# LPC55S69_MINI_A.net
KiCad netlist of a schematic drawn in Altium Designer
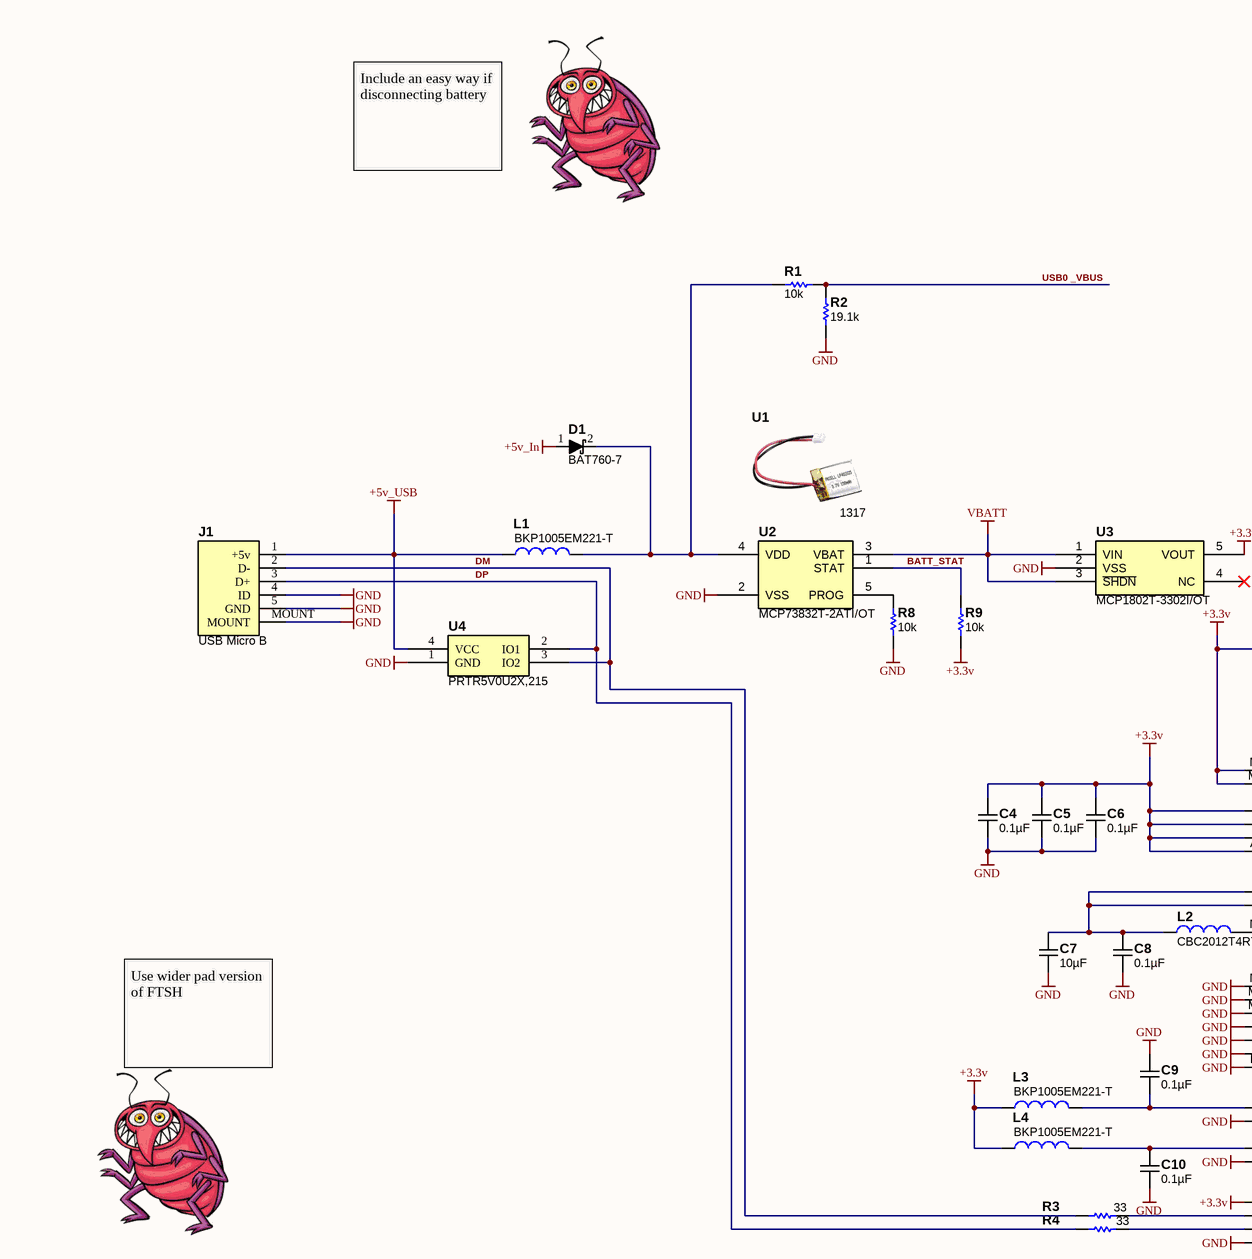
[diagram p0: LPC55S69_MINI [A].SchDoc, top left]
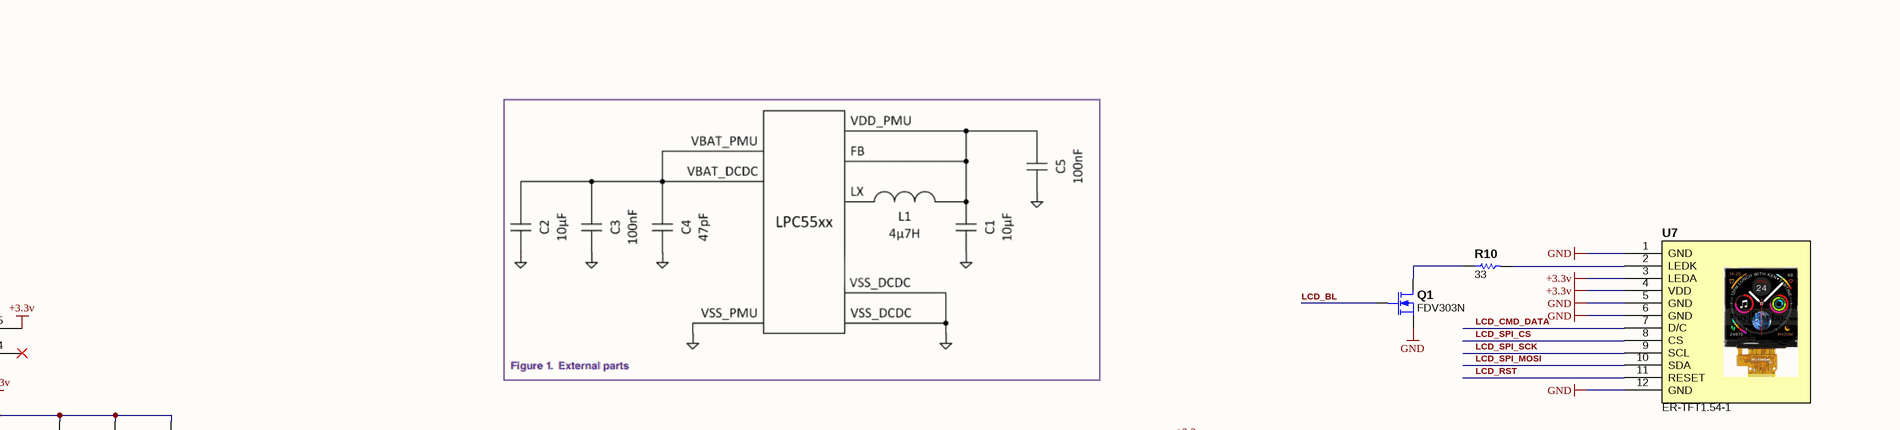
[diagram p1: LPC55S69_MINI [A].SchDoc, top right]
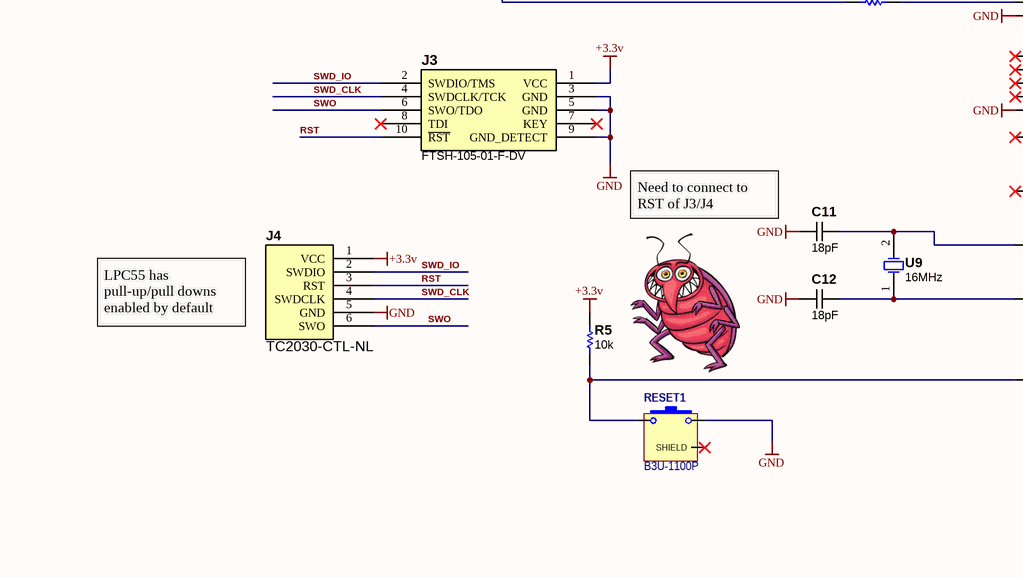
[diagram p2: LPC55S69_MINI [A].SchDoc, bottom left]
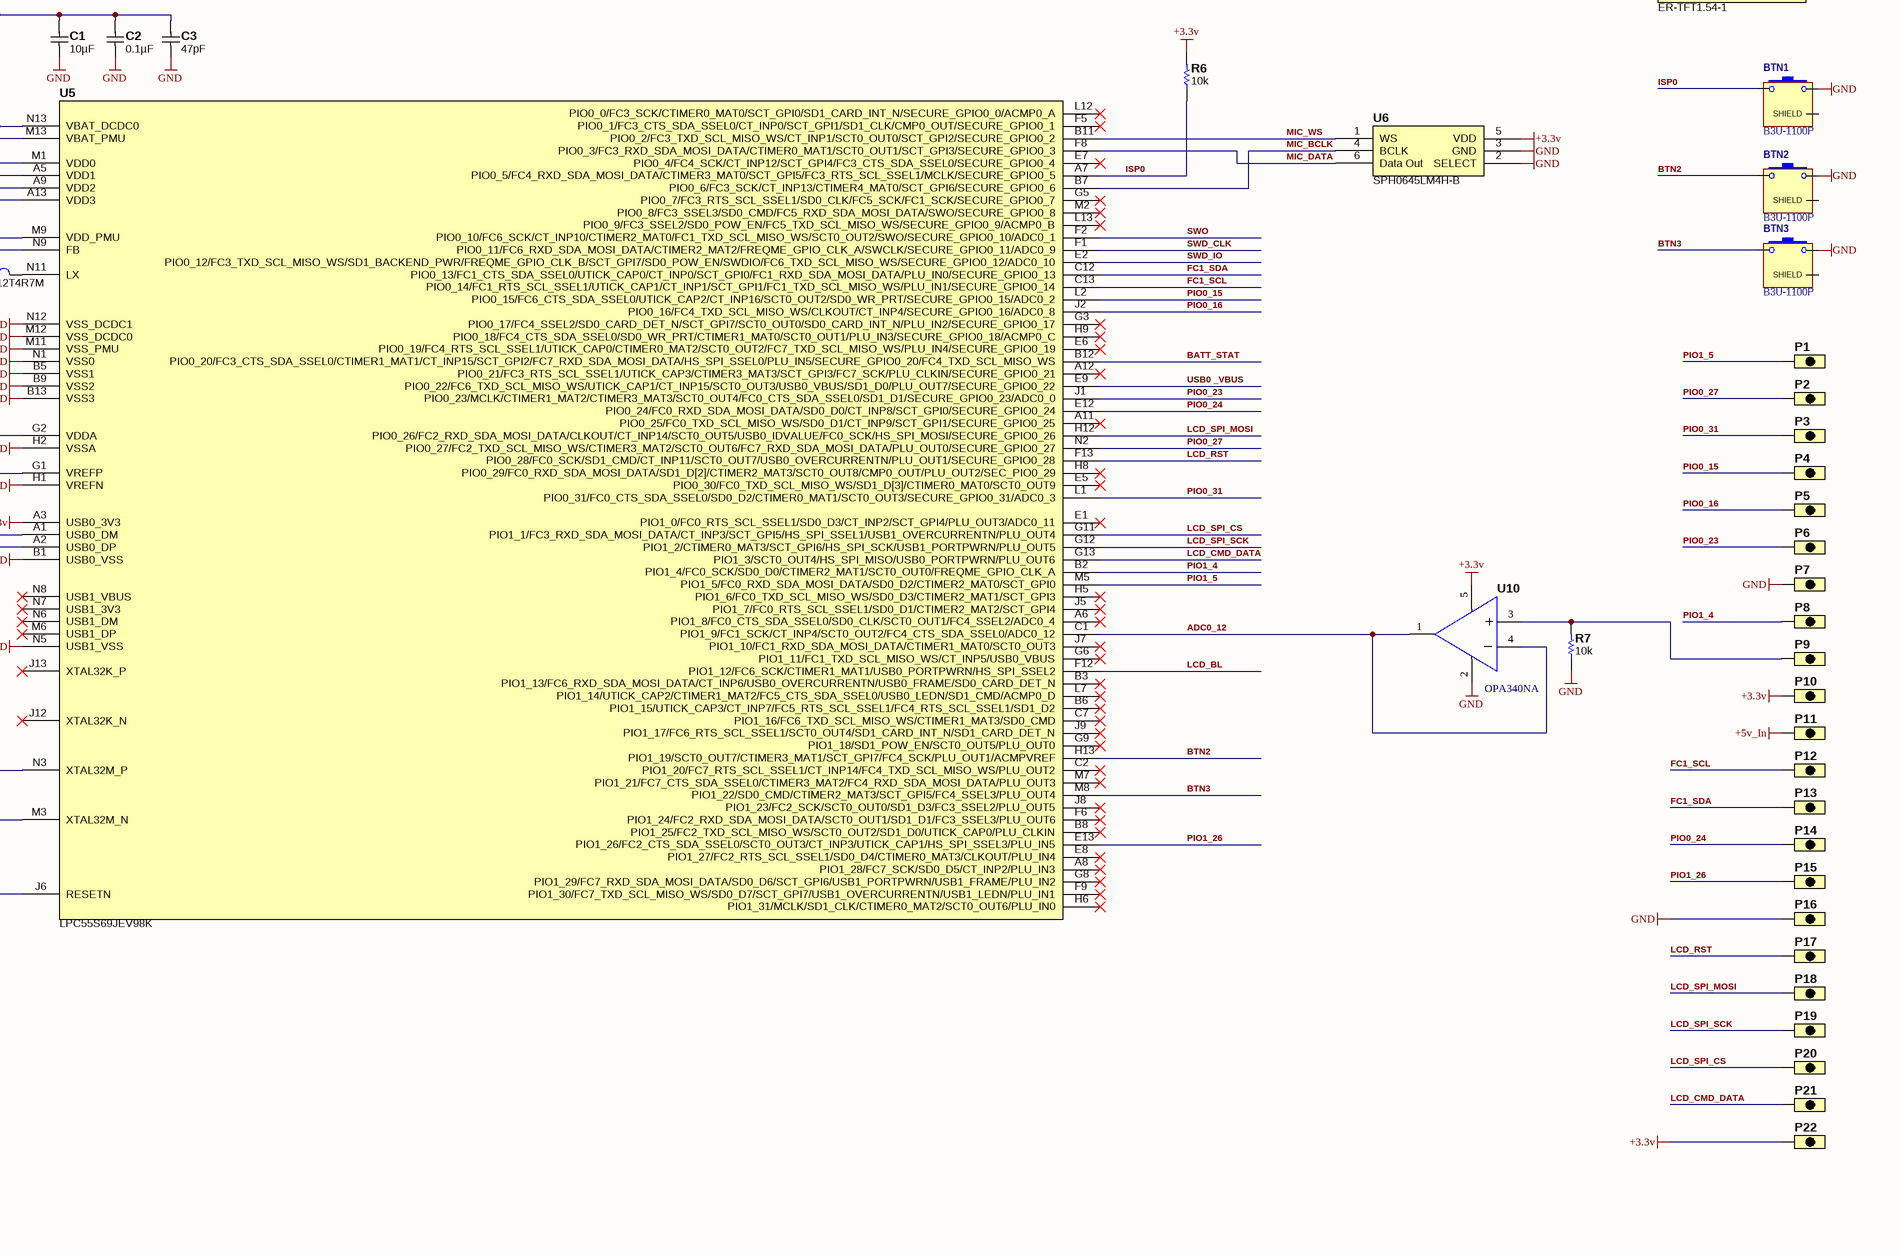
[diagram p3: LPC55S69_MINI [A].SchDoc, bottom right]

(export (version "E")
  (design (tool "Eeschema 10.0.6"))
  (components
    (comp (ref "BTN1")
      (value "B3U-1100P")
      (footprint "OMRON_B3U-1100P")
      (description "SWITCH TACTILE SPST-NO 0.05A 12V")
      (fields (field (name "MANUFACTURER") "Omron Electronics Inc-EMC Div"))
      (libsource (lib "Switches-N") (part "B3U-1100P"))
    )
    (comp (ref "BTN2")
      (value "B3U-1100P")
      (footprint "OMRON_B3U-1100P")
      (description "SWITCH TACTILE SPST-NO 0.05A 12V")
      (fields (field (name "MANUFACTURER") "Omron Electronics Inc-EMC Div"))
      (libsource (lib "Switches-N") (part "B3U-1100P"))
    )
    (comp (ref "BTN3")
      (value "B3U-1100P")
      (footprint "OMRON_B3U-1100P")
      (description "SWITCH TACTILE SPST-NO 0.05A 12V")
      (fields (field (name "MANUFACTURER") "Omron Electronics Inc-EMC Div"))
      (libsource (lib "Switches-N") (part "B3U-1100P"))
    )
    (comp (ref "C1")
      (value "10µF")
      (footprint "C0805_1.45MM_MD")
      (description "CAP CER 10UF 6.3V X7R 0805")
      (fields
        (field (name "MANUFACTURER PART NUMBER") "CGA4J1X7R0J106K125AC")
        (field (name "MANUFACTURER") "TDK Corporation")
      )
      (libsource (lib "Capacitors - TDK- AEC-Q200") (part "C_2P_NP"))
    )
    (comp (ref "C2")
      (value "0.1µF")
      (footprint "C0402_0.55MM_MD")
      (description "CAP CER 0.1UF 16V X7R 0402")
      (fields
        (field (name "MANUFACTURER PART NUMBER") "CGA2B1X7R1C104K050BC")
        (field (name "MANUFACTURER") "TDK Corporation")
      )
      (libsource (lib "Capacitors - TDK- AEC-Q200") (part "C_2P_NP"))
    )
    (comp (ref "C3")
      (value "47pF")
      (footprint "C0402_0.55MM_MD")
      (description "CAP CER 47PF 50V C0G 0402")
      (fields
        (field (name "MANUFACTURER PART NUMBER") "CGA2B2C0G1H470J050BA")
        (field (name "MANUFACTURER") "TDK Corporation")
      )
      (libsource (lib "Capacitors - TDK- AEC-Q200") (part "C_2P_NP"))
    )
    (comp (ref "C4")
      (value "0.1µF")
      (footprint "C0402_0.55MM_MD")
      (description "CAP CER 0.1UF 16V X7R 0402")
      (fields
        (field (name "MANUFACTURER PART NUMBER") "CGA2B1X7R1C104K050BC")
        (field (name "MANUFACTURER") "TDK Corporation")
      )
      (libsource (lib "Capacitors - TDK- AEC-Q200") (part "C_2P_NP"))
    )
    (comp (ref "C5")
      (value "0.1µF")
      (footprint "C0402_0.55MM_MD")
      (description "CAP CER 0.1UF 16V X7R 0402")
      (fields
        (field (name "MANUFACTURER PART NUMBER") "CGA2B1X7R1C104K050BC")
        (field (name "MANUFACTURER") "TDK Corporation")
      )
      (libsource (lib "Capacitors - TDK- AEC-Q200") (part "C_2P_NP"))
    )
    (comp (ref "C6")
      (value "0.1µF")
      (footprint "C0402_0.55MM_MD")
      (description "CAP CER 0.1UF 16V X7R 0402")
      (fields
        (field (name "MANUFACTURER PART NUMBER") "CGA2B1X7R1C104K050BC")
        (field (name "MANUFACTURER") "TDK Corporation")
      )
      (libsource (lib "Capacitors - TDK- AEC-Q200") (part "C_2P_NP"))
    )
    (comp (ref "C7")
      (value "10µF")
      (footprint "C0805_1.45MM_MD")
      (description "CAP CER 10UF 6.3V X7R 0805")
      (fields
        (field (name "MANUFACTURER PART NUMBER") "CGA4J1X7R0J106K125AC")
        (field (name "MANUFACTURER") "TDK Corporation")
      )
      (libsource (lib "Capacitors - TDK- AEC-Q200") (part "C_2P_NP"))
    )
    (comp (ref "C8")
      (value "0.1µF")
      (footprint "C0402_0.55MM_MD")
      (description "CAP CER 0.1UF 16V X7R 0402")
      (fields
        (field (name "MANUFACTURER PART NUMBER") "CGA2B1X7R1C104K050BC")
        (field (name "MANUFACTURER") "TDK Corporation")
      )
      (libsource (lib "Capacitors - TDK- AEC-Q200") (part "C_2P_NP"))
    )
    (comp (ref "C9")
      (value "0.1µF")
      (footprint "C0402_0.55MM_MD")
      (description "CAP CER 0.1UF 16V X7R 0402")
      (fields
        (field (name "MANUFACTURER PART NUMBER") "CGA2B1X7R1C104K050BC")
        (field (name "MANUFACTURER") "TDK Corporation")
      )
      (libsource (lib "Capacitors - TDK- AEC-Q200") (part "C_2P_NP"))
    )
    (comp (ref "C10")
      (value "0.1µF")
      (footprint "C0402_0.55MM_MD")
      (description "CAP CER 0.1UF 16V X7R 0402")
      (fields
        (field (name "MANUFACTURER PART NUMBER") "CGA2B1X7R1C104K050BC")
        (field (name "MANUFACTURER") "TDK Corporation")
      )
      (libsource (lib "Capacitors - TDK- AEC-Q200") (part "C_2P_NP"))
    )
    (comp (ref "C11")
      (value "18pF")
      (footprint "C0402_0.55MM_MD")
      (description "CAP CER 18PF 50V C0G 0402")
      (fields
        (field (name "MANUFACTURER PART NUMBER") "CGA2B2C0G1H180J050BA")
        (field (name "MANUFACTURER") "TDK Corporation")
      )
      (libsource (lib "Capacitors - TDK- AEC-Q200") (part "C_2P_NP"))
    )
    (comp (ref "C12")
      (value "18pF")
      (footprint "C0402_0.55MM_MD")
      (description "CAP CER 18PF 50V C0G 0402")
      (fields
        (field (name "MANUFACTURER PART NUMBER") "CGA2B2C0G1H180J050BA")
        (field (name "MANUFACTURER") "TDK Corporation")
      )
      (libsource (lib "Capacitors - TDK- AEC-Q200") (part "C_2P_NP"))
    )
    (comp (ref "D1")
      (value "BAT760-7")
      (footprint "D_SOD-323_P")
      (description "DIODE SCHOTTKY 30V 1A SOD323")
      (fields (field (name "MANUFACTURER") "Diodes Inc"))
      (libsource (lib "Diodes") (part "DS_1A_2C"))
    )
    (comp (ref "J1")
      (value "USB Micro B")
      (footprint "10103594-0001LF")
      (description "CONN RCPT STD MICRO USB TYPE B")
      (fields (field (name "MANUFACTURER") "FCI") (field (name "MANUFACTURER PART NUMBER") "10103594-0001LF"))
      (libsource (lib "eConnector_USB") (part "10103594-0001LF"))
    )
    (comp (ref "J3")
      (value "FTSH-105-01-F-DV")
      (footprint "FTSH-105-04-F-DV - HD - NO_STEP")
      (description "SAMTEC - FTSH-105-01-F-DV - .050 X .050")
      (fields (field (name "MANUFACTURER") "SAMTEC"))
      (libsource (lib "eConnector") (part "CORTEX-DEBUG"))
    )
    (comp (ref "J4")
      (value "TC2030‐CTL‐NL")
      (footprint "TC2030 NO LATCH")
      (description "Tag Connect Pads - No latching Clips - ARM")
      (libsource (lib "eConnector") (part "TC2030‐CTL‐NL"))
    )
    (comp (ref "L1")
      (value "BKP1005EM221-T")
      (footprint "C0402_HD")
      (description "FERRITE BEAD 220 OHM 0402 1LN")
      (fields (field (name "MANUFACTURER") "Taiyo Yuden"))
      (libsource (lib "eInductor") (part "BKP1005EM221-T"))
    )
    (comp (ref "L2")
      (value "CBC2012T4R7M")
      (footprint "C0805_1.45MM_MD")
      (description "FIXED IND 4.7UH 520MA 650 MOHM")
      (fields (field (name "MANUFACTURER") "Taiyo Yuden") (field (name "TOLERANCE") "20%"))
      (libsource (lib "eInductor") (part "CBC2012T4R7M"))
    )
    (comp (ref "L3")
      (value "BKP1005EM221-T")
      (footprint "C0402_HD")
      (description "FERRITE BEAD 220 OHM 0402 1LN")
      (fields (field (name "MANUFACTURER") "Taiyo Yuden"))
      (libsource (lib "eInductor") (part "BKP1005EM221-T"))
    )
    (comp (ref "L4")
      (value "BKP1005EM221-T")
      (footprint "C0402_HD")
      (description "FERRITE BEAD 220 OHM 0402 1LN")
      (fields (field (name "MANUFACTURER") "Taiyo Yuden"))
      (libsource (lib "eInductor") (part "BKP1005EM221-T"))
    )
    (comp (ref "P1")
      (value "~")
      (footprint "CASTELLATED")
      (libsource (lib "eConnector") (part "CASTELLATED"))
    )
    (comp (ref "P2")
      (value "~")
      (footprint "CASTELLATED")
      (libsource (lib "eConnector") (part "CASTELLATED"))
    )
    (comp (ref "P3")
      (value "~")
      (footprint "CASTELLATED")
      (libsource (lib "eConnector") (part "CASTELLATED"))
    )
    (comp (ref "P4")
      (value "~")
      (footprint "CASTELLATED")
      (libsource (lib "eConnector") (part "CASTELLATED"))
    )
    (comp (ref "P5")
      (value "~")
      (footprint "CASTELLATED")
      (libsource (lib "eConnector") (part "CASTELLATED"))
    )
    (comp (ref "P6")
      (value "~")
      (footprint "CASTELLATED")
      (libsource (lib "eConnector") (part "CASTELLATED"))
    )
    (comp (ref "P7")
      (value "~")
      (footprint "CASTELLATED")
      (libsource (lib "eConnector") (part "CASTELLATED"))
    )
    (comp (ref "P8")
      (value "~")
      (footprint "CASTELLATED")
      (libsource (lib "eConnector") (part "CASTELLATED"))
    )
    (comp (ref "P9")
      (value "~")
      (footprint "CASTELLATED")
      (libsource (lib "eConnector") (part "CASTELLATED"))
    )
    (comp (ref "P10")
      (value "~")
      (footprint "CASTELLATED")
      (libsource (lib "eConnector") (part "CASTELLATED"))
    )
    (comp (ref "P11")
      (value "~")
      (footprint "CASTELLATED")
      (libsource (lib "eConnector") (part "CASTELLATED"))
    )
    (comp (ref "P12")
      (value "~")
      (footprint "CASTELLATED")
      (libsource (lib "eConnector") (part "CASTELLATED"))
    )
    (comp (ref "P13")
      (value "~")
      (footprint "CASTELLATED")
      (libsource (lib "eConnector") (part "CASTELLATED"))
    )
    (comp (ref "P14")
      (value "~")
      (footprint "CASTELLATED")
      (libsource (lib "eConnector") (part "CASTELLATED"))
    )
    (comp (ref "P15")
      (value "~")
      (footprint "CASTELLATED")
      (libsource (lib "eConnector") (part "CASTELLATED"))
    )
    (comp (ref "P16")
      (value "~")
      (footprint "CASTELLATED")
      (libsource (lib "eConnector") (part "CASTELLATED"))
    )
    (comp (ref "P17")
      (value "~")
      (footprint "CASTELLATED")
      (libsource (lib "eConnector") (part "CASTELLATED"))
    )
    (comp (ref "P18")
      (value "~")
      (footprint "CASTELLATED")
      (libsource (lib "eConnector") (part "CASTELLATED"))
    )
    (comp (ref "P19")
      (value "~")
      (footprint "CASTELLATED")
      (libsource (lib "eConnector") (part "CASTELLATED"))
    )
    (comp (ref "P20")
      (value "~")
      (footprint "CASTELLATED")
      (libsource (lib "eConnector") (part "CASTELLATED"))
    )
    (comp (ref "P21")
      (value "~")
      (footprint "CASTELLATED")
      (libsource (lib "eConnector") (part "CASTELLATED"))
    )
    (comp (ref "P22")
      (value "~")
      (footprint "CASTELLATED")
      (libsource (lib "eConnector") (part "CASTELLATED"))
    )
    (comp (ref "Q1")
      (value "FDV303N")
      (footprint "SOT-23")
      (description "MOSFET N-CH 25V 680MA SOT-23")
      (fields (field (name "MANUFACTURER") "Fairchild Semiconductor") (field (name "SOURCE") "Digikey"))
      (libsource (lib "eTransistor") (part "FDV303N"))
    )
    (comp (ref "R1")
      (value "10k")
      (footprint "R0402_0.40MM_MD")
      (description "RES 10K OHM 1/10W 1% 0402 SMD")
      (fields
        (field (name "MANUFACTURER PART NUMBER") "ERJ-2RKF1002X")
        (field (name "MANUFACTURER") "Panasonic Electronic Components")
      )
      (libsource (lib "Resistors - Panasonic - AEC-Q200") (part "R_2P"))
    )
    (comp (ref "R2")
      (value "19.1k")
      (footprint "R0402_0.40MM_MD")
      (description "RES 19.1K OHM 1/10W 1% 0402 SMD")
      (fields
        (field (name "MANUFACTURER PART NUMBER") "ERJ-2RKF1912X")
        (field (name "MANUFACTURER") "Panasonic Electronic Components")
      )
      (libsource (lib "Resistors - Panasonic - AEC-Q200") (part "R_2P"))
    )
    (comp (ref "R3")
      (value "33")
      (footprint "R0603_0.55MM_MD")
      (description "RES 33 OHM 1/10W 1% 0603 SMD")
      (fields
        (field (name "MANUFACTURER PART NUMBER") "ERJ-3EKF33R0V")
        (field (name "MANUFACTURER") "Panasonic Electronic Components")
      )
      (libsource (lib "Resistors - Panasonic - AEC-Q200") (part "R_2P"))
    )
    (comp (ref "R4")
      (value "33")
      (footprint "R0603_0.55MM_MD")
      (description "RES 33 OHM 1/10W 1% 0603 SMD")
      (fields
        (field (name "MANUFACTURER PART NUMBER") "ERJ-3EKF33R0V")
        (field (name "MANUFACTURER") "Panasonic Electronic Components")
      )
      (libsource (lib "Resistors - Panasonic - AEC-Q200") (part "R_2P"))
    )
    (comp (ref "R5")
      (value "10k")
      (footprint "R0402_0.40MM_MD")
      (description "RES 10K OHM 1/10W 1% 0402 SMD")
      (fields
        (field (name "MANUFACTURER PART NUMBER") "ERJ-2RKF1002X")
        (field (name "MANUFACTURER") "Panasonic Electronic Components")
      )
      (libsource (lib "Resistors - Panasonic - AEC-Q200") (part "R_2P"))
    )
    (comp (ref "R6")
      (value "10k")
      (footprint "R0402_0.40MM_MD")
      (description "RES 10K OHM 1/10W 1% 0402 SMD")
      (fields
        (field (name "MANUFACTURER PART NUMBER") "ERJ-2RKF1002X")
        (field (name "MANUFACTURER") "Panasonic Electronic Components")
      )
      (libsource (lib "Resistors - Panasonic - AEC-Q200") (part "R_2P"))
    )
    (comp (ref "R7")
      (value "10k")
      (footprint "R0402_0.40MM_MD")
      (description "RES 10K OHM 1/10W 1% 0402 SMD")
      (fields
        (field (name "MANUFACTURER PART NUMBER") "ERJ-2RKF1002X")
        (field (name "MANUFACTURER") "Panasonic Electronic Components")
      )
      (libsource (lib "Resistors - Panasonic - AEC-Q200") (part "R_2P"))
    )
    (comp (ref "R8")
      (value "10k")
      (footprint "R0402_0.40MM_MD")
      (description "RES 10K OHM 1/10W 1% 0402 SMD")
      (fields
        (field (name "MANUFACTURER PART NUMBER") "ERJ-2RKF1002X")
        (field (name "MANUFACTURER") "Panasonic Electronic Components")
      )
      (libsource (lib "Resistors - Panasonic - AEC-Q200") (part "R_2P"))
    )
    (comp (ref "R9")
      (value "10k")
      (footprint "R0402_0.40MM_MD")
      (description "RES 10K OHM 1/10W 1% 0402 SMD")
      (fields
        (field (name "MANUFACTURER PART NUMBER") "ERJ-2RKF1002X")
        (field (name "MANUFACTURER") "Panasonic Electronic Components")
      )
      (libsource (lib "Resistors - Panasonic - AEC-Q200") (part "R_2P"))
    )
    (comp (ref "R10")
      (value "33")
      (footprint "R0603_0.55MM_MD")
      (description "RES 33 OHM 1/10W 1% 0603 SMD")
      (fields
        (field (name "MANUFACTURER PART NUMBER") "ERJ-3EKF33R0V")
        (field (name "MANUFACTURER") "Panasonic Electronic Components")
      )
      (libsource (lib "Resistors - Panasonic - AEC-Q200") (part "R_2P"))
    )
    (comp (ref "RESET1")
      (value "B3U-1100P")
      (footprint "OMRON_B3U-1100P")
      (description "SWITCH TACTILE SPST-NO 0.05A 12V")
      (fields (field (name "MANUFACTURER") "Omron Electronics Inc-EMC Div"))
      (libsource (lib "Switches-N") (part "B3U-1100P"))
    )
    (comp (ref "U1")
      (value "1317")
      (footprint "LIPO-150MAH")
      (description "FLORA LI-PO BATTERY 3.7V 150MAH")
      (fields (field (name "MANUFACTURER") "Adafruit Industries"))
      (libsource (lib "eBattery") (part "1317"))
    )
    (comp (ref "U2")
      (value "MCP73832T-2ATI/OT")
      (footprint "SOT23-5")
      (description "Charge Controller Li-Ion/Li-Pol 15mA to 500mA 4.2V 5-Pin SOT-23 T/R")
      (fields (field (name "MANUFACTURER") "Microchip"))
      (libsource (lib "eIC") (part "MCP73832T-2ATI/OT"))
    )
    (comp (ref "U3")
      (value "MCP1802T-3302I/OT")
      (footprint "SOT23-5")
      (description "IC REG LINEAR 3.3V 300MA SOT23-5")
      (fields (field (name "MANUFACTURER") "Microchip"))
      (libsource (lib "eIC_Regulator") (part "MCP1802T-3302I/OT"))
    )
    (comp (ref "U4")
      (value "PRTR5V0U2X,215")
      (footprint "SOT143B")
      (description "TVS DIODE 5.5VWM SOT143B")
      (fields (field (name "MANUFACTURER") "NXP Semiconductors"))
      (libsource (lib "eDiode") (part "PRTR5V0U2X,215"))
    )
    (comp (ref "U5")
      (value "LPC55S69JEV98K")
      (footprint "98-VFBGA")
      (description "IC MCU 100MHZ CORTEX M33 DUAL")
      (fields (field (name "MANUFACTURER") "NXP Semiconductors"))
      (libsource (lib "eIC") (part "LPC55S69JEV98K"))
    )
    (comp (ref "U6")
      (value "SPH0645LM4H-B")
      (footprint "SPH0645LM4H-B")
      (fields (field (name "MANUFACTURER") "Knowles Acoustics"))
      (libsource (lib "eAudio") (part "SPH0645LM4H-B"))
    )
    (comp (ref "U7")
      (value "ER-TFT1.54-1")
      (footprint "ER-TFT1.54-1")
      (description "1.54\" 240x240 IPS Display")
      (fields (field (name "MANUFACTURER") "Buy Display"))
      (libsource (lib "eDisplay") (part "ER-TFT1.54-1"))
    )
    (comp (ref "U9")
      (value "16MHz")
      (footprint "ABM3")
      (description "Crystal 16MHz ±20ppm (Tol) ±50ppm (Stability) 18pF FUND 50Ohm 2-Pin CSMD T/R")
      (fields
        (field (name "MANUFACTURER") "Abracon")
        (field (name "MANUFACTURER PART NUMBER") "ABM3-16.000MHZ-B2-T")
      )
      (libsource (lib "eCrystal") (part "ABM3-16.000MHZ-B2-T"))
    )
    (comp (ref "U10")
      (value "OPA340NA")
      (footprint "SOT95P245X145-5L")
      (description "IC SINGLE SUPPLY OPAMP SOT-23-5")
      (fields
        (field (name "MANUFACTURER") "Texas Instruments")
        (field (name "MANUFACTURER PART NUMBER") "OPA340NA/250")
        (field (name "SOURCE") "Digikey")
      )
      (libsource (lib "eOPAMP") (part "OPA340"))
    )
  )
  (nets
    (net (code "1") (name "+3.3v") (class "Default")
      (node (ref "C1") (pin "2") (pinfunction "1_2") (pintype "passive"))
      (node (ref "C2") (pin "2") (pinfunction "1_2") (pintype "passive"))
      (node (ref "C3") (pin "2") (pinfunction "1_2") (pintype "passive"))
      (node (ref "C4") (pin "2") (pinfunction "1_2") (pintype "passive"))
      (node (ref "C5") (pin "2") (pinfunction "1_2") (pintype "passive"))
      (node (ref "C6") (pin "2") (pinfunction "1_2") (pintype "passive"))
      (node (ref "J3") (pin "1") (pinfunction "VCC_1") (pintype "passive"))
      (node (ref "J4") (pin "1") (pinfunction "VCC_1") (pintype "passive"))
      (node (ref "L3") (pin "1") (pinfunction "1_1") (pintype "passive"))
      (node (ref "L4") (pin "1") (pinfunction "1_1") (pintype "passive"))
      (node (ref "P10") (pin "1") (pinfunction "1_1") (pintype "passive"))
      (node (ref "P22") (pin "1") (pinfunction "1_1") (pintype "passive"))
      (node (ref "R5") (pin "2") (pinfunction "2_2") (pintype "passive"))
      (node (ref "R6") (pin "2") (pinfunction "2_2") (pintype "passive"))
      (node (ref "R9") (pin "1") (pinfunction "1_1") (pintype "passive"))
      (node (ref "U10") (pin "5") (pinfunction "VCC_5") (pintype "passive"))
      (node (ref "U3") (pin "5") (pinfunction "VOUT_5") (pintype "passive"))
      (node (ref "U5") (pin "A13") (pinfunction "VDD3_A13") (pintype "passive"))
      (node (ref "U5") (pin "A3") (pinfunction "USB0_3V3_A3") (pintype "passive"))
      (node (ref "U5") (pin "A5") (pinfunction "VDD1_A5") (pintype "passive"))
      (node (ref "U5") (pin "A9") (pinfunction "VDD2_A9") (pintype "passive"))
      (node (ref "U5") (pin "M1") (pinfunction "VDD0_M1") (pintype "passive"))
      (node (ref "U5") (pin "M13") (pinfunction "VBAT_PMU_M13") (pintype "passive"))
      (node (ref "U5") (pin "N13") (pinfunction "VBAT_DCDC0_N13") (pintype "passive"))
      (node (ref "U6") (pin "5") (pinfunction "VDD_5") (pintype "passive"))
      (node (ref "U7") (pin "3") (pinfunction "LEDA_3") (pintype "passive"))
      (node (ref "U7") (pin "4") (pinfunction "VDD_4") (pintype "passive"))
    )
    (net (code "2") (name "+5v_In") (class "Default")
      (node (ref "D1") (pin "1") (pinfunction "A_1") (pintype "passive"))
      (node (ref "P11") (pin "1") (pinfunction "1_1") (pintype "passive"))
    )
    (net (code "3") (name "+5v_USB") (class "Default")
      (node (ref "J1") (pin "1") (pinfunction "+5v_1") (pintype "passive"))
      (node (ref "L1") (pin "1") (pinfunction "1_1") (pintype "passive"))
      (node (ref "U4") (pin "4") (pinfunction "VCC_4") (pintype "passive"))
    )
    (net (code "4") (name "/ADC0_12") (class "Default")
      (node (ref "U10") (pin "1") (pinfunction "OUT_1") (pintype "passive"))
      (node (ref "U10") (pin "4") (pinfunction "-_4") (pintype "passive"))
      (node (ref "U5") (pin "C1") (pinfunction "PIO1_9/FC1_SCK/CT_INP4/SCT0_OUT2/FC4_CTS_SDA_SSEL0/ADC0_12_C1") (pintype "passive"))
    )
    (net (code "5") (name "/BATT_STAT") (class "Default")
      (node (ref "R9") (pin "2") (pinfunction "2_2") (pintype "passive"))
      (node (ref "U2") (pin "1") (pinfunction "STAT_1") (pintype "passive"))
      (node (ref "U5") (pin "B12") (pinfunction "PIO0_20/FC3_CTS_SDA_SSEL0/CTIMER1_MAT1/CT_INP15/SCT_GPI2/FC7_RXD_SDA_MOSI_DATA/HS_SPI_SSEL0/PLU_IN5/SECURE_GPIO0_20/FC4_TXD_SCL_MISO_WS_B12") (pintype "passive"))
    )
    (net (code "6") (name "/BTN2") (class "Default")
      (node (ref "BTN2") (pin "2") (pinfunction "2_2") (pintype "passive"))
      (node (ref "U5") (pin "H13") (pinfunction "PIO1_19/SCT0_OUT7/CTIMER3_MAT1/SCT_GPI7/FC4_SCK/PLU_OUT1/ACMPVREF_H13") (pintype "passive"))
    )
    (net (code "7") (name "/BTN3") (class "Default")
      (node (ref "BTN3") (pin "2") (pinfunction "2_2") (pintype "passive"))
      (node (ref "U5") (pin "M8") (pinfunction "PIO1_22/SD0_CMD/CTIMER2_MAT3/SCT_GPI5/FC4_SSEL3/PLU_OUT4_M8") (pintype "passive"))
    )
    (net (code "8") (name "/DM") (class "Default")
      (node (ref "J1") (pin "2") (pinfunction "D-_2") (pintype "passive"))
      (node (ref "R3") (pin "1") (pinfunction "1_1") (pintype "passive"))
      (node (ref "U4") (pin "3") (pinfunction "IO2_3") (pintype "passive"))
    )
    (net (code "9") (name "/DP") (class "Default")
      (node (ref "J1") (pin "3") (pinfunction "D+_3") (pintype "passive"))
      (node (ref "R4") (pin "1") (pinfunction "1_1") (pintype "passive"))
      (node (ref "U4") (pin "2") (pinfunction "IO1_2") (pintype "passive"))
    )
    (net (code "10") (name "/FC1_SCL") (class "Default")
      (node (ref "P12") (pin "1") (pinfunction "1_1") (pintype "passive"))
      (node (ref "U5") (pin "C13") (pinfunction "PIO0_14/FC1_RTS_SCL_SSEL1/UTICK_CAP1/CT_INP1/SCT_GPI1/FC1_TXD_SCL_MISO_WS/PLU_IN1/SECURE_GPIO0_14_C13") (pintype "passive"))
    )
    (net (code "11") (name "/FC1_SDA") (class "Default")
      (node (ref "P13") (pin "1") (pinfunction "1_1") (pintype "passive"))
      (node (ref "U5") (pin "C12") (pinfunction "PIO0_13/FC1_CTS_SDA_SSEL0/UTICK_CAP0/CT_INP0/SCT_GPI0/FC1_RXD_SDA_MOSI_DATA/PLU_IN0/SECURE_GPIO0_13_C12") (pintype "passive"))
    )
    (net (code "12") (name "/ISP0") (class "Default")
      (node (ref "BTN1") (pin "2") (pinfunction "2_2") (pintype "passive"))
      (node (ref "R6") (pin "1") (pinfunction "1_1") (pintype "passive"))
      (node (ref "U5") (pin "A7") (pinfunction "PIO0_5/FC4_RXD_SDA_MOSI_DATA/CTIMER3_MAT0/SCT_GPI5/FC3_RTS_SCL_SSEL1/MCLK/SECURE_GPIO0_5_A7") (pintype "passive"))
    )
    (net (code "13") (name "/LCD_BL") (class "Default")
      (node (ref "Q1") (pin "1") (pinfunction "G_1") (pintype "passive"))
      (node (ref "U5") (pin "F12") (pinfunction "PIO1_12/FC6_SCK/CTIMER1_MAT1/USB0_PORTPWRN/HS_SPI_SSEL2_F12") (pintype "passive"))
    )
    (net (code "14") (name "/LCD_CMD_DATA") (class "Default")
      (node (ref "P21") (pin "1") (pinfunction "1_1") (pintype "passive"))
      (node (ref "U5") (pin "G13") (pinfunction "PIO1_3/SCT0_OUT4/HS_SPI_MISO/USB0_PORTPWRN/PLU_OUT6_G13") (pintype "passive"))
      (node (ref "U7") (pin "7") (pinfunction "D/C_7") (pintype "passive"))
    )
    (net (code "15") (name "/LCD_RST") (class "Default")
      (node (ref "P17") (pin "1") (pinfunction "1_1") (pintype "passive"))
      (node (ref "U5") (pin "F13") (pinfunction "PIO0_28/FC0_SCK/SD1_CMD/CT_INP11/SCT0_OUT7/USB0_OVERCURRENTN/PLU_OUT1/SECURE_GPIO0_28_F13") (pintype "passive"))
      (node (ref "U7") (pin "11") (pinfunction "RESET_11") (pintype "passive"))
    )
    (net (code "16") (name "/LCD_SPI_CS") (class "Default")
      (node (ref "P20") (pin "1") (pinfunction "1_1") (pintype "passive"))
      (node (ref "U5") (pin "G11") (pinfunction "PIO1_1/FC3_RXD_SDA_MOSI_DATA/CT_INP3/SCT_GPI5/HS_SPI_SSEL1/USB1_OVERCURRENTN/PLU_OUT4_G11") (pintype "passive"))
      (node (ref "U7") (pin "8") (pinfunction "CS_8") (pintype "passive"))
    )
    (net (code "17") (name "/LCD_SPI_MOSI") (class "Default")
      (node (ref "P18") (pin "1") (pinfunction "1_1") (pintype "passive"))
      (node (ref "U5") (pin "H12") (pinfunction "PIO0_26/FC2_RXD_SDA_MOSI_DATA/CLKOUT/CT_INP14/SCT0_OUT5/USB0_IDVALUE/FC0_SCK/HS_SPI_MOSI/SECURE_GPIO0_26_H12") (pintype "passive"))
      (node (ref "U7") (pin "10") (pinfunction "SDA_10") (pintype "passive"))
    )
    (net (code "18") (name "/LCD_SPI_SCK") (class "Default")
      (node (ref "P19") (pin "1") (pinfunction "1_1") (pintype "passive"))
      (node (ref "U5") (pin "G12") (pinfunction "PIO1_2/CTIMER0_MAT3/SCT_GPI6/HS_SPI_SCK/USB1_PORTPWRN/PLU_OUT5_G12") (pintype "passive"))
      (node (ref "U7") (pin "9") (pinfunction "SCL_9") (pintype "passive"))
    )
    (net (code "19") (name "/MIC_BCLK") (class "Default")
      (node (ref "U5") (pin "B7") (pinfunction "PIO0_6/FC3_SCK/CT_INP13/CTIMER4_MAT0/SCT_GPI6/SECURE_GPIO0_6_B7") (pintype "passive"))
      (node (ref "U6") (pin "4") (pinfunction "BCLK_4") (pintype "passive"))
    )
    (net (code "20") (name "/MIC_DATA") (class "Default")
      (node (ref "U5") (pin "F8") (pinfunction "PIO0_3/FC3_RXD_SDA_MOSI_DATA/CTIMER0_MAT1/SCT0_OUT1/SCT_GPI3/SECURE_GPIO0_3_F8") (pintype "passive"))
      (node (ref "U6") (pin "6") (pinfunction "Data_Out_6") (pintype "passive"))
    )
    (net (code "21") (name "/MIC_WS") (class "Default")
      (node (ref "U5") (pin "B11") (pinfunction "PIO0_2/FC3_TXD_SCL_MISO_WS/CT_INP1/SCT0_OUT0/SCT_GPI2/SECURE_GPIO0_2_B11") (pintype "passive"))
      (node (ref "U6") (pin "1") (pinfunction "WS_1") (pintype "passive"))
    )
    (net (code "22") (name "/PIO0_15") (class "Default")
      (node (ref "P4") (pin "1") (pinfunction "1_1") (pintype "passive"))
      (node (ref "U5") (pin "L2") (pinfunction "PIO0_15/FC6_CTS_SDA_SSEL0/UTICK_CAP2/CT_INP16/SCT0_OUT2/SD0_WR_PRT/SECURE_GPIO0_15/ADC0_2_L2") (pintype "passive"))
    )
    (net (code "23") (name "/PIO0_16") (class "Default")
      (node (ref "P5") (pin "1") (pinfunction "1_1") (pintype "passive"))
      (node (ref "U5") (pin "J2") (pinfunction "PIO0_16/FC4_TXD_SCL_MISO_WS/CLKOUT/CT_INP4/SECURE_GPIO0_16/ADC0_8_J2") (pintype "passive"))
    )
    (net (code "24") (name "/PIO0_23") (class "Default")
      (node (ref "P6") (pin "1") (pinfunction "1_1") (pintype "passive"))
      (node (ref "U5") (pin "J1") (pinfunction "PIO0_23/MCLK/CTIMER1_MAT2/CTIMER3_MAT3/SCT0_OUT4/FC0_CTS_SDA_SSEL0/SD1_D1/SECURE_GPIO0_23/ADC0_0_J1") (pintype "passive"))
    )
    (net (code "25") (name "/PIO0_24") (class "Default")
      (node (ref "P14") (pin "1") (pinfunction "1_1") (pintype "passive"))
      (node (ref "U5") (pin "E12") (pinfunction "PIO0_24/FC0_RXD_SDA_MOSI_DATA/SD0_D0/CT_INP8/SCT_GPI0/SECURE_GPIO0_24_E12") (pintype "passive"))
    )
    (net (code "26") (name "/PIO0_27") (class "Default")
      (node (ref "P2") (pin "1") (pinfunction "1_1") (pintype "passive"))
      (node (ref "U5") (pin "N2") (pinfunction "PIO0_27/FC2_TXD_SCL_MISO_WS/CTIMER3_MAT2/SCT0_OUT6/FC7_RXD_SDA_MOSI_DATA/PLU_OUT0/SECURE_GPIO0_27_N2") (pintype "passive"))
    )
    (net (code "27") (name "/PIO0_31") (class "Default")
      (node (ref "P3") (pin "1") (pinfunction "1_1") (pintype "passive"))
      (node (ref "U5") (pin "L1") (pinfunction "PIO0_31/FC0_CTS_SDA_SSEL0/SD0_D2/CTIMER0_MAT1/SCT0_OUT3/SECURE_GPIO0_31/ADC0_3_L1") (pintype "passive"))
    )
    (net (code "28") (name "/PIO1_4") (class "Default")
      (node (ref "P8") (pin "1") (pinfunction "1_1") (pintype "passive"))
      (node (ref "U5") (pin "B2") (pinfunction "PIO1_4/FC0_SCK/SD0_D0/CTIMER2_MAT1/SCT0_OUT0/FREQME_GPIO_CLK_A_B2") (pintype "passive"))
    )
    (net (code "29") (name "/PIO1_5") (class "Default")
      (node (ref "P1") (pin "1") (pinfunction "1_1") (pintype "passive"))
      (node (ref "U5") (pin "M5") (pinfunction "PIO1_5/FC0_RXD_SDA_MOSI_DATA/SD0_D2/CTIMER2_MAT0/SCT_GPI0_M5") (pintype "passive"))
    )
    (net (code "30") (name "/PIO1_26") (class "Default")
      (node (ref "P15") (pin "1") (pinfunction "1_1") (pintype "passive"))
      (node (ref "U5") (pin "E13") (pinfunction "PIO1_26/FC2_CTS_SDA_SSEL0/SCT0_OUT3/CT_INP3/UTICK_CAP1/HS_SPI_SSEL3/PLU_IN5_E13") (pintype "passive"))
    )
    (net (code "31") (name "/RST") (class "Default")
      (node (ref "J3") (pin "10") (pinfunction "~{RST}_10") (pintype "passive"))
      (node (ref "J4") (pin "3") (pinfunction "RST_3") (pintype "passive"))
    )
    (net (code "32") (name "/SWD_CLK") (class "Default")
      (node (ref "J3") (pin "4") (pinfunction "SWDCLK/TCK_4") (pintype "passive"))
      (node (ref "J4") (pin "4") (pinfunction "SWDCLK_4") (pintype "passive"))
      (node (ref "U5") (pin "F1") (pinfunction "PIO0_11/FC6_RXD_SDA_MOSI_DATA/CTIMER2_MAT2/FREQME_GPIO_CLK_A/SWCLK/SECURE_GPIO0_11/ADC0_9_F1") (pintype "passive"))
    )
    (net (code "33") (name "/SWD_IO") (class "Default")
      (node (ref "J3") (pin "2") (pinfunction "SWDIO/TMS_2") (pintype "passive"))
      (node (ref "J4") (pin "2") (pinfunction "SWDIO_2") (pintype "passive"))
      (node (ref "U5") (pin "E2") (pinfunction "PIO0_12/FC3_TXD_SCL_MISO_WS/SD1_BACKEND_PWR/FREQME_GPIO_CLK_B/SCT_GPI7/SD0_POW_EN/SWDIO/FC6_TXD_SCL_MISO_WS/SECURE_GPIO0_12/ADC0_10_E2") (pintype "passive"))
    )
    (net (code "34") (name "/SWO") (class "Default")
      (node (ref "J3") (pin "6") (pinfunction "SWO/TDO_6") (pintype "passive"))
      (node (ref "J4") (pin "6") (pinfunction "SWO_6") (pintype "passive"))
      (node (ref "U5") (pin "F2") (pinfunction "PIO0_10/FC6_SCK/CT_INP10/CTIMER2_MAT0/FC1_TXD_SCL_MISO_WS/SCT0_OUT2/SWO/SECURE_GPIO0_10/ADC0_1_F2") (pintype "passive"))
    )
    (net (code "35") (name "/USB0 _VBUS") (class "Default")
      (node (ref "R1") (pin "2") (pinfunction "2_2") (pintype "passive"))
      (node (ref "R2") (pin "2") (pinfunction "2_2") (pintype "passive"))
      (node (ref "U5") (pin "E9") (pinfunction "PIO0_22/FC6_TXD_SCL_MISO_WS/UTICK_CAP1/CT_INP15/SCT0_OUT3/USB0_VBUS/SD1_D0/PLU_OUT7/SECURE_GPIO0_22_E9") (pintype "passive"))
    )
    (net (code "36") (name "GND") (class "Default")
      (node (ref "BTN1") (pin "1") (pinfunction "1_1") (pintype "passive"))
      (node (ref "BTN2") (pin "1") (pinfunction "1_1") (pintype "passive"))
      (node (ref "BTN3") (pin "1") (pinfunction "1_1") (pintype "passive"))
      (node (ref "C1") (pin "1") (pinfunction "1_1") (pintype "passive"))
      (node (ref "C10") (pin "1") (pinfunction "1_1") (pintype "passive"))
      (node (ref "C11") (pin "1") (pinfunction "1_1") (pintype "passive"))
      (node (ref "C12") (pin "1") (pinfunction "1_1") (pintype "passive"))
      (node (ref "C2") (pin "1") (pinfunction "1_1") (pintype "passive"))
      (node (ref "C3") (pin "1") (pinfunction "1_1") (pintype "passive"))
      (node (ref "C4") (pin "1") (pinfunction "1_1") (pintype "passive"))
      (node (ref "C5") (pin "1") (pinfunction "1_1") (pintype "passive"))
      (node (ref "C6") (pin "1") (pinfunction "1_1") (pintype "passive"))
      (node (ref "C7") (pin "1") (pinfunction "1_1") (pintype "passive"))
      (node (ref "C8") (pin "1") (pinfunction "1_1") (pintype "passive"))
      (node (ref "C9") (pin "2") (pinfunction "1_2") (pintype "passive"))
      (node (ref "J1") (pin "4") (pinfunction "ID_4") (pintype "passive"))
      (node (ref "J1") (pin "5") (pinfunction "GND_5") (pintype "passive"))
      (node (ref "J1") (pin "MOUNT") (pinfunction "MOUNT_MOUNT") (pintype "passive"))
      (node (ref "J3") (pin "3") (pinfunction "GND_3") (pintype "passive"))
      (node (ref "J3") (pin "5") (pinfunction "GND_5") (pintype "passive"))
      (node (ref "J3") (pin "9") (pinfunction "GND_DETECT_9") (pintype "passive"))
      (node (ref "J4") (pin "5") (pinfunction "GND_5") (pintype "passive"))
      (node (ref "P16") (pin "1") (pinfunction "1_1") (pintype "passive"))
      (node (ref "P7") (pin "1") (pinfunction "1_1") (pintype "passive"))
      (node (ref "Q1") (pin "2") (pinfunction "S_2") (pintype "passive"))
      (node (ref "R2") (pin "1") (pinfunction "1_1") (pintype "passive"))
      (node (ref "R7") (pin "1") (pinfunction "1_1") (pintype "passive"))
      (node (ref "R8") (pin "1") (pinfunction "1_1") (pintype "passive"))
      (node (ref "RESET1") (pin "1") (pinfunction "1_1") (pintype "passive"))
      (node (ref "U10") (pin "2") (pinfunction "GND_2") (pintype "passive"))
      (node (ref "U2") (pin "2") (pinfunction "VSS_2") (pintype "passive"))
      (node (ref "U3") (pin "2") (pinfunction "VSS_2") (pintype "passive"))
      (node (ref "U4") (pin "1") (pinfunction "GND_1") (pintype "passive"))
      (node (ref "U5") (pin "B1") (pinfunction "USB0_VSS_B1") (pintype "passive"))
      (node (ref "U5") (pin "B13") (pinfunction "VSS3_B13") (pintype "passive"))
      (node (ref "U5") (pin "B5") (pinfunction "VSS1_B5") (pintype "passive"))
      (node (ref "U5") (pin "B9") (pinfunction "VSS2_B9") (pintype "passive"))
      (node (ref "U5") (pin "H1") (pinfunction "VREFN_H1") (pintype "passive"))
      (node (ref "U5") (pin "H2") (pinfunction "VSSA_H2") (pintype "passive"))
      (node (ref "U5") (pin "M11") (pinfunction "VSS_PMU_M11") (pintype "passive"))
      (node (ref "U5") (pin "M12") (pinfunction "VSS_DCDC0_M12") (pintype "passive"))
      (node (ref "U5") (pin "N1") (pinfunction "VSS0_N1") (pintype "passive"))
      (node (ref "U5") (pin "N12") (pinfunction "VSS_DCDC1_N12") (pintype "passive"))
      (node (ref "U5") (pin "N5") (pinfunction "USB1_VSS_N5") (pintype "passive"))
      (node (ref "U6") (pin "2") (pinfunction "SELECT_2") (pintype "passive"))
      (node (ref "U6") (pin "3") (pinfunction "GND_3") (pintype "passive"))
      (node (ref "U7") (pin "1") (pinfunction "GND_1") (pintype "passive"))
      (node (ref "U7") (pin "12") (pinfunction "GND_12") (pintype "passive"))
      (node (ref "U7") (pin "5") (pinfunction "GND_5") (pintype "passive"))
      (node (ref "U7") (pin "6") (pinfunction "GND_6") (pintype "passive"))
    )
    (net (code "37") (name "Net-(D1-K)") (class "Default")
      (node (ref "D1") (pin "2") (pinfunction "K_2") (pintype "passive"))
      (node (ref "L1") (pin "2") (pinfunction "2_2") (pintype "passive"))
      (node (ref "R1") (pin "1") (pinfunction "1_1") (pintype "passive"))
      (node (ref "U2") (pin "4") (pinfunction "VDD_4") (pintype "passive"))
    )
    (net (code "38") (name "Net-(Q1-D)") (class "Default")
      (node (ref "Q1") (pin "3") (pinfunction "D_3") (pintype "passive"))
      (node (ref "R10") (pin "1") (pinfunction "1_1") (pintype "passive"))
    )
    (net (code "39") (name "Net-(U2-PROG)") (class "Default")
      (node (ref "R8") (pin "2") (pinfunction "2_2") (pintype "passive"))
      (node (ref "U2") (pin "5") (pinfunction "PROG_5") (pintype "passive"))
    )
    (net (code "40") (name "Net-(U5-FB)") (class "Default")
      (node (ref "C7") (pin "2") (pinfunction "1_2") (pintype "passive"))
      (node (ref "C8") (pin "2") (pinfunction "1_2") (pintype "passive"))
      (node (ref "L2") (pin "1") (pinfunction "1_1") (pintype "passive"))
      (node (ref "U5") (pin "M9") (pinfunction "VDD_PMU_M9") (pintype "passive"))
      (node (ref "U5") (pin "N9") (pinfunction "FB_N9") (pintype "passive"))
    )
    (net (code "41") (name "Net-(U5-LX)") (class "Default")
      (node (ref "L2") (pin "2") (pinfunction "2_2") (pintype "passive"))
      (node (ref "U5") (pin "N11") (pinfunction "LX_N11") (pintype "passive"))
    )
    (net (code "42") (name "Net-(U5-RESETN)") (class "Default")
      (node (ref "R5") (pin "1") (pinfunction "1_1") (pintype "passive"))
      (node (ref "RESET1") (pin "2") (pinfunction "2_2") (pintype "passive"))
      (node (ref "U5") (pin "J6") (pinfunction "RESETN_J6") (pintype "passive"))
    )
    (net (code "43") (name "Net-(U5-USB0_DM)") (class "Default")
      (node (ref "R3") (pin "2") (pinfunction "2_2") (pintype "passive"))
      (node (ref "U5") (pin "A1") (pinfunction "USB0_DM_A1") (pintype "passive"))
    )
    (net (code "44") (name "Net-(U5-USB0_DP)") (class "Default")
      (node (ref "R4") (pin "2") (pinfunction "2_2") (pintype "passive"))
      (node (ref "U5") (pin "A2") (pinfunction "USB0_DP_A2") (pintype "passive"))
    )
    (net (code "45") (name "Net-(U5-VDDA)") (class "Default")
      (node (ref "C9") (pin "1") (pinfunction "1_1") (pintype "passive"))
      (node (ref "L3") (pin "2") (pinfunction "2_2") (pintype "passive"))
      (node (ref "U5") (pin "G2") (pinfunction "VDDA_G2") (pintype "passive"))
    )
    (net (code "46") (name "Net-(U5-VREFP)") (class "Default")
      (node (ref "C10") (pin "2") (pinfunction "1_2") (pintype "passive"))
      (node (ref "L4") (pin "2") (pinfunction "2_2") (pintype "passive"))
      (node (ref "U5") (pin "G1") (pinfunction "VREFP_G1") (pintype "passive"))
    )
    (net (code "47") (name "Net-(U5-XTAL32M_N)") (class "Default")
      (node (ref "C12") (pin "2") (pinfunction "1_2") (pintype "passive"))
      (node (ref "U5") (pin "M3") (pinfunction "XTAL32M_N_M3") (pintype "passive"))
      (node (ref "U9") (pin "1") (pinfunction "OSC1_1") (pintype "passive"))
    )
    (net (code "48") (name "Net-(U5-XTAL32M_P)") (class "Default")
      (node (ref "C11") (pin "2") (pinfunction "1_2") (pintype "passive"))
      (node (ref "U5") (pin "N3") (pinfunction "XTAL32M_P_N3") (pintype "passive"))
      (node (ref "U9") (pin "2") (pinfunction "OSC2_2") (pintype "passive"))
    )
    (net (code "49") (name "Net-(U7-LEDK)") (class "Default")
      (node (ref "R10") (pin "2") (pinfunction "2_2") (pintype "passive"))
      (node (ref "U7") (pin "2") (pinfunction "LEDK_2") (pintype "passive"))
    )
    (net (code "50") (name "Net-(U10-+)") (class "Default")
      (node (ref "P9") (pin "1") (pinfunction "1_1") (pintype "passive"))
      (node (ref "R7") (pin "2") (pinfunction "2_2") (pintype "passive"))
      (node (ref "U10") (pin "3") (pinfunction "+_3") (pintype "passive"))
    )
    (net (code "51") (name "VBATT") (class "Default")
      (node (ref "U2") (pin "3") (pinfunction "VBAT_3") (pintype "passive"))
      (node (ref "U3") (pin "1") (pinfunction "VIN_1") (pintype "passive"))
      (node (ref "U3") (pin "3") (pinfunction "~{SHDN}_3") (pintype "passive"))
    )
    (net (code "52") (name "unconnected-(BTN1-SHIELD-PadS)") (class "Default")
      (node (ref "BTN1") (pin "S") (pinfunction "SHIELD_S") (pintype "passive"))
    )
    (net (code "53") (name "unconnected-(BTN2-SHIELD-PadS)") (class "Default")
      (node (ref "BTN2") (pin "S") (pinfunction "SHIELD_S") (pintype "passive"))
    )
    (net (code "54") (name "unconnected-(BTN3-SHIELD-PadS)") (class "Default")
      (node (ref "BTN3") (pin "S") (pinfunction "SHIELD_S") (pintype "passive"))
    )
    (net (code "55") (name "unconnected-(J3-KEY-Pad7)") (class "Default")
      (node (ref "J3") (pin "7") (pinfunction "KEY_7") (pintype "passive+no_connect"))
    )
    (net (code "56") (name "unconnected-(J3-TDI-Pad8)") (class "Default")
      (node (ref "J3") (pin "8") (pinfunction "TDI_8") (pintype "passive+no_connect"))
    )
    (net (code "57") (name "unconnected-(RESET1-SHIELD-PadS)") (class "Default")
      (node (ref "RESET1") (pin "S") (pinfunction "SHIELD_S") (pintype "passive+no_connect"))
    )
    (net (code "58") (name "unconnected-(U3-NC-Pad4)") (class "Default")
      (node (ref "U3") (pin "4") (pinfunction "NC_4") (pintype "passive+no_connect"))
    )
    (net (code "59") (name "unconnected-(U5-PIO0_0{slash}FC3_SCK{slash}CTIMER0_MAT0{slash}SCT_GPI0{slash}SD1_CARD_INT_N{slash}SECURE_GPIO0_0{slash}ACMP0_A-PadL12)") (class "Default")
      (node (ref "U5") (pin "L12") (pinfunction "PIO0_0/FC3_SCK/CTIMER0_MAT0/SCT_GPI0/SD1_CARD_INT_N/SECURE_GPIO0_0/ACMP0_A_L12") (pintype "passive+no_connect"))
    )
    (net (code "60") (name "unconnected-(U5-PIO0_1{slash}FC3_CTS_SDA_SSEL0{slash}CT_INP0{slash}SCT_GPI1{slash}SD1_CLK{slash}CMP0_OUT{slash}SECURE_GPIO0_1-PadF5)") (class "Default")
      (node (ref "U5") (pin "F5") (pinfunction "PIO0_1/FC3_CTS_SDA_SSEL0/CT_INP0/SCT_GPI1/SD1_CLK/CMP0_OUT/SECURE_GPIO0_1_F5") (pintype "passive+no_connect"))
    )
    (net (code "61") (name "unconnected-(U5-PIO0_4{slash}FC4_SCK{slash}CT_INP12{slash}SCT_GPI4{slash}FC3_CTS_SDA_SSEL0{slash}SECURE_GPIO0_4-PadE7)") (class "Default")
      (node (ref "U5") (pin "E7") (pinfunction "PIO0_4/FC4_SCK/CT_INP12/SCT_GPI4/FC3_CTS_SDA_SSEL0/SECURE_GPIO0_4_E7") (pintype "passive+no_connect"))
    )
    (net (code "62") (name "unconnected-(U5-PIO0_7{slash}FC3_RTS_SCL_SSEL1{slash}SD0_CLK{slash}FC5_SCK{slash}FC1_SCK{slash}SECURE_GPIO0_7-PadG5)") (class "Default")
      (node (ref "U5") (pin "G5") (pinfunction "PIO0_7/FC3_RTS_SCL_SSEL1/SD0_CLK/FC5_SCK/FC1_SCK/SECURE_GPIO0_7_G5") (pintype "passive+no_connect"))
    )
    (net (code "63") (name "unconnected-(U5-PIO0_8{slash}FC3_SSEL3{slash}SD0_CMD{slash}FC5_RXD_SDA_MOSI_DATA{slash}SWO{slash}SECURE_GPIO0_8-PadM2)") (class "Default")
      (node (ref "U5") (pin "M2") (pinfunction "PIO0_8/FC3_SSEL3/SD0_CMD/FC5_RXD_SDA_MOSI_DATA/SWO/SECURE_GPIO0_8_M2") (pintype "passive+no_connect"))
    )
    (net (code "64") (name "unconnected-(U5-PIO0_9{slash}FC3_SSEL2{slash}SD0_POW_EN{slash}FC5_TXD_SCL_MISO_WS{slash}SECURE_GPIO0_9{slash}ACMP0_B-PadL13)") (class "Default")
      (node (ref "U5") (pin "L13") (pinfunction "PIO0_9/FC3_SSEL2/SD0_POW_EN/FC5_TXD_SCL_MISO_WS/SECURE_GPIO0_9/ACMP0_B_L13") (pintype "passive+no_connect"))
    )
    (net (code "65") (name "unconnected-(U5-PIO0_17{slash}FC4_SSEL2{slash}SD0_CARD_DET_N{slash}SCT_GPI7{slash}SCT0_OUT0{slash}SD0_CARD_INT_N{slash}PLU_IN2{slash}SECURE_GPIO0_17-PadG3)") (class "Default")
      (node (ref "U5") (pin "G3") (pinfunction "PIO0_17/FC4_SSEL2/SD0_CARD_DET_N/SCT_GPI7/SCT0_OUT0/SD0_CARD_INT_N/PLU_IN2/SECURE_GPIO0_17_G3") (pintype "passive+no_connect"))
    )
    (net (code "66") (name "unconnected-(U5-PIO0_18{slash}FC4_CTS_SDA_SSEL0{slash}SD0_WR_PRT{slash}CTIMER1_MAT0{slash}SCT0_OUT1{slash}PLU_IN3{slash}SECURE_GPIO0_18{slash}ACMP0_C-PadH9)") (class "Default")
      (node (ref "U5") (pin "H9") (pinfunction "PIO0_18/FC4_CTS_SDA_SSEL0/SD0_WR_PRT/CTIMER1_MAT0/SCT0_OUT1/PLU_IN3/SECURE_GPIO0_18/ACMP0_C_H9") (pintype "passive+no_connect"))
    )
    (net (code "67") (name "unconnected-(U5-PIO0_19{slash}FC4_RTS_SCL_SSEL1{slash}UTICK_CAP0{slash}CTIMER0_MAT2{slash}SCT0_OUT2{slash}FC7_TXD_SCL_MISO_WS{slash}PLU_IN4{slash}SECURE_GPIO0_19-PadE6)") (class "Default")
      (node (ref "U5") (pin "E6") (pinfunction "PIO0_19/FC4_RTS_SCL_SSEL1/UTICK_CAP0/CTIMER0_MAT2/SCT0_OUT2/FC7_TXD_SCL_MISO_WS/PLU_IN4/SECURE_GPIO0_19_E6") (pintype "passive+no_connect"))
    )
    (net (code "68") (name "unconnected-(U5-PIO0_21{slash}FC3_RTS_SCL_SSEL1{slash}UTICK_CAP3{slash}CTIMER3_MAT3{slash}SCT_GPI3{slash}FC7_SCK{slash}PLU_CLKIN{slash}SECURE_GPIO0_21-PadA12)") (class "Default")
      (node (ref "U5") (pin "A12") (pinfunction "PIO0_21/FC3_RTS_SCL_SSEL1/UTICK_CAP3/CTIMER3_MAT3/SCT_GPI3/FC7_SCK/PLU_CLKIN/SECURE_GPIO0_21_A12") (pintype "passive+no_connect"))
    )
    (net (code "69") (name "unconnected-(U5-PIO0_25{slash}FC0_TXD_SCL_MISO_WS{slash}SD0_D1{slash}CT_INP9{slash}SCT_GPI1{slash}SECURE_GPIO0_25-PadA11)") (class "Default")
      (node (ref "U5") (pin "A11") (pinfunction "PIO0_25/FC0_TXD_SCL_MISO_WS/SD0_D1/CT_INP9/SCT_GPI1/SECURE_GPIO0_25_A11") (pintype "passive+no_connect"))
    )
    (net (code "70") (name "unconnected-(U5-PIO0_29{slash}FC0_RXD_SDA_MOSI_DATA{slash}SD1_D[2]{slash}CTIMER2_MAT3{slash}SCT0_OUT8{slash}CMP0_OUT{slash}PLU_OUT2{slash}SEC_PIO0_29-PadH8)") (class "Default")
      (node (ref "U5") (pin "H8") (pinfunction "PIO0_29/FC0_RXD_SDA_MOSI_DATA/SD1_D[2]/CTIMER2_MAT3/SCT0_OUT8/CMP0_OUT/PLU_OUT2/SEC_PIO0_29_H8") (pintype "passive+no_connect"))
    )
    (net (code "71") (name "unconnected-(U5-PIO0_30{slash}FC0_TXD_SCL_MISO_WS{slash}SD1_D[3]{slash}CTIMER0_MAT0{slash}SCT0_OUT9-PadE5)") (class "Default")
      (node (ref "U5") (pin "E5") (pinfunction "PIO0_30/FC0_TXD_SCL_MISO_WS/SD1_D[3]/CTIMER0_MAT0/SCT0_OUT9_E5") (pintype "passive+no_connect"))
    )
    (net (code "72") (name "unconnected-(U5-PIO1_0{slash}FC0_RTS_SCL_SSEL1{slash}SD0_D3{slash}CT_INP2{slash}SCT_GPI4{slash}PLU_OUT3{slash}ADC0_11-PadE1)") (class "Default")
      (node (ref "U5") (pin "E1") (pinfunction "PIO1_0/FC0_RTS_SCL_SSEL1/SD0_D3/CT_INP2/SCT_GPI4/PLU_OUT3/ADC0_11_E1") (pintype "passive+no_connect"))
    )
    (net (code "73") (name "unconnected-(U5-PIO1_6{slash}FC0_TXD_SCL_MISO_WS{slash}SD0_D3{slash}CTIMER2_MAT1{slash}SCT_GPI3-PadH5)") (class "Default")
      (node (ref "U5") (pin "H5") (pinfunction "PIO1_6/FC0_TXD_SCL_MISO_WS/SD0_D3/CTIMER2_MAT1/SCT_GPI3_H5") (pintype "passive+no_connect"))
    )
    (net (code "74") (name "unconnected-(U5-PIO1_7{slash}FC0_RTS_SCL_SSEL1{slash}SD0_D1{slash}CTIMER2_MAT2{slash}SCT_GPI4-PadJ5)") (class "Default")
      (node (ref "U5") (pin "J5") (pinfunction "PIO1_7/FC0_RTS_SCL_SSEL1/SD0_D1/CTIMER2_MAT2/SCT_GPI4_J5") (pintype "passive+no_connect"))
    )
    (net (code "75") (name "unconnected-(U5-PIO1_8{slash}FC0_CTS_SDA_SSEL0{slash}SD0_CLK{slash}SCT0_OUT1{slash}FC4_SSEL2{slash}ADC0_4-PadA6)") (class "Default")
      (node (ref "U5") (pin "A6") (pinfunction "PIO1_8/FC0_CTS_SDA_SSEL0/SD0_CLK/SCT0_OUT1/FC4_SSEL2/ADC0_4_A6") (pintype "passive+no_connect"))
    )
    (net (code "76") (name "unconnected-(U5-PIO1_10{slash}FC1_RXD_SDA_MOSI_DATA{slash}CTIMER1_MAT0{slash}SCT0_OUT3-PadJ7)") (class "Default")
      (node (ref "U5") (pin "J7") (pinfunction "PIO1_10/FC1_RXD_SDA_MOSI_DATA/CTIMER1_MAT0/SCT0_OUT3_J7") (pintype "passive+no_connect"))
    )
    (net (code "77") (name "unconnected-(U5-PIO1_11{slash}FC1_TXD_SCL_MISO_WS{slash}CT_INP5{slash}USB0_VBUS-PadG6)") (class "Default")
      (node (ref "U5") (pin "G6") (pinfunction "PIO1_11/FC1_TXD_SCL_MISO_WS/CT_INP5/USB0_VBUS_G6") (pintype "passive+no_connect"))
    )
    (net (code "78") (name "unconnected-(U5-PIO1_13{slash}FC6_RXD_SDA_MOSI_DATA{slash}CT_INP6{slash}USB0_OVERCURRENTN{slash}USB0_FRAME{slash}SD0_CARD_DET_N-PadB3)") (class "Default")
      (node (ref "U5") (pin "B3") (pinfunction "PIO1_13/FC6_RXD_SDA_MOSI_DATA/CT_INP6/USB0_OVERCURRENTN/USB0_FRAME/SD0_CARD_DET_N_B3") (pintype "passive+no_connect"))
    )
    (net (code "79") (name "unconnected-(U5-PIO1_14{slash}UTICK_CAP2{slash}CTIMER1_MAT2{slash}FC5_CTS_SDA_SSEL0{slash}USB0_LEDN{slash}SD1_CMD{slash}ACMP0_D-PadL7)") (class "Default")
      (node (ref "U5") (pin "L7") (pinfunction "PIO1_14/UTICK_CAP2/CTIMER1_MAT2/FC5_CTS_SDA_SSEL0/USB0_LEDN/SD1_CMD/ACMP0_D_L7") (pintype "passive+no_connect"))
    )
    (net (code "80") (name "unconnected-(U5-PIO1_15{slash}UTICK_CAP3{slash}CT_INP7{slash}FC5_RTS_SCL_SSEL1{slash}FC4_RTS_SCL_SSEL1{slash}SD1_D2-PadB6)") (class "Default")
      (node (ref "U5") (pin "B6") (pinfunction "PIO1_15/UTICK_CAP3/CT_INP7/FC5_RTS_SCL_SSEL1/FC4_RTS_SCL_SSEL1/SD1_D2_B6") (pintype "passive+no_connect"))
    )
    (net (code "81") (name "unconnected-(U5-PIO1_16{slash}FC6_TXD_SCL_MISO_WS{slash}CTIMER1_MAT3{slash}SD0_CMD-PadC7)") (class "Default")
      (node (ref "U5") (pin "C7") (pinfunction "PIO1_16/FC6_TXD_SCL_MISO_WS/CTIMER1_MAT3/SD0_CMD_C7") (pintype "passive+no_connect"))
    )
    (net (code "82") (name "unconnected-(U5-PIO1_17{slash}FC6_RTS_SCL_SSEL1{slash}SCT0_OUT4{slash}SD1_CARD_INT_N{slash}SD1_CARD_DET_N-PadJ9)") (class "Default")
      (node (ref "U5") (pin "J9") (pinfunction "PIO1_17/FC6_RTS_SCL_SSEL1/SCT0_OUT4/SD1_CARD_INT_N/SD1_CARD_DET_N_J9") (pintype "passive+no_connect"))
    )
    (net (code "83") (name "unconnected-(U5-PIO1_18{slash}SD1_POW_EN{slash}SCT0_OUT5{slash}PLU_OUT0-PadG9)") (class "Default")
      (node (ref "U5") (pin "G9") (pinfunction "PIO1_18/SD1_POW_EN/SCT0_OUT5/PLU_OUT0_G9") (pintype "passive+no_connect"))
    )
    (net (code "84") (name "unconnected-(U5-PIO1_20{slash}FC7_RTS_SCL_SSEL1{slash}CT_INP14{slash}FC4_TXD_SCL_MISO_WS{slash}PLU_OUT2-PadC2)") (class "Default")
      (node (ref "U5") (pin "C2") (pinfunction "PIO1_20/FC7_RTS_SCL_SSEL1/CT_INP14/FC4_TXD_SCL_MISO_WS/PLU_OUT2_C2") (pintype "passive+no_connect"))
    )
    (net (code "85") (name "unconnected-(U5-PIO1_21{slash}FC7_CTS_SDA_SSEL0{slash}CTIMER3_MAT2{slash}FC4_RXD_SDA_MOSI_DATA{slash}PLU_OUT3-PadM7)") (class "Default")
      (node (ref "U5") (pin "M7") (pinfunction "PIO1_21/FC7_CTS_SDA_SSEL0/CTIMER3_MAT2/FC4_RXD_SDA_MOSI_DATA/PLU_OUT3_M7") (pintype "passive+no_connect"))
    )
    (net (code "86") (name "unconnected-(U5-PIO1_23{slash}FC2_SCK{slash}SCT0_OUT0{slash}SD1_D3{slash}FC3_SSEL2{slash}PLU_OUT5-PadJ8)") (class "Default")
      (node (ref "U5") (pin "J8") (pinfunction "PIO1_23/FC2_SCK/SCT0_OUT0/SD1_D3/FC3_SSEL2/PLU_OUT5_J8") (pintype "passive+no_connect"))
    )
    (net (code "87") (name "unconnected-(U5-PIO1_24{slash}FC2_RXD_SDA_MOSI_DATA{slash}SCT0_OUT1{slash}SD1_D1{slash}FC3_SSEL3{slash}PLU_OUT6-PadF6)") (class "Default")
      (node (ref "U5") (pin "F6") (pinfunction "PIO1_24/FC2_RXD_SDA_MOSI_DATA/SCT0_OUT1/SD1_D1/FC3_SSEL3/PLU_OUT6_F6") (pintype "passive+no_connect"))
    )
    (net (code "88") (name "unconnected-(U5-PIO1_25{slash}FC2_TXD_SCL_MISO_WS{slash}SCT0_OUT2{slash}SD1_D0{slash}UTICK_CAP0{slash}PLU_CLKIN-PadB8)") (class "Default")
      (node (ref "U5") (pin "B8") (pinfunction "PIO1_25/FC2_TXD_SCL_MISO_WS/SCT0_OUT2/SD1_D0/UTICK_CAP0/PLU_CLKIN_B8") (pintype "passive+no_connect"))
    )
    (net (code "89") (name "unconnected-(U5-PIO1_27{slash}FC2_RTS_SCL_SSEL1{slash}SD0_D4{slash}CTIMER0_MAT3{slash}CLKOUT{slash}PLU_IN4-PadE8)") (class "Default")
      (node (ref "U5") (pin "E8") (pinfunction "PIO1_27/FC2_RTS_SCL_SSEL1/SD0_D4/CTIMER0_MAT3/CLKOUT/PLU_IN4_E8") (pintype "passive+no_connect"))
    )
    (net (code "90") (name "unconnected-(U5-PIO1_28{slash}FC7_SCK{slash}SD0_D5{slash}CT_INP2{slash}PLU_IN3-PadA8)") (class "Default")
      (node (ref "U5") (pin "A8") (pinfunction "PIO1_28/FC7_SCK/SD0_D5/CT_INP2/PLU_IN3_A8") (pintype "passive+no_connect"))
    )
    (net (code "91") (name "unconnected-(U5-PIO1_29{slash}FC7_RXD_SDA_MOSI_DATA{slash}SD0_D6{slash}SCT_GPI6{slash}USB1_PORTPWRN{slash}USB1_FRAME{slash}PLU_IN2-PadG8)") (class "Default")
      (node (ref "U5") (pin "G8") (pinfunction "PIO1_29/FC7_RXD_SDA_MOSI_DATA/SD0_D6/SCT_GPI6/USB1_PORTPWRN/USB1_FRAME/PLU_IN2_G8") (pintype "passive+no_connect"))
    )
    (net (code "92") (name "unconnected-(U5-PIO1_30{slash}FC7_TXD_SCL_MISO_WS{slash}SD0_D7{slash}SCT_GPI7{slash}USB1_OVERCURRENTN{slash}USB1_LEDN{slash}PLU_IN1-PadF9)") (class "Default")
      (node (ref "U5") (pin "F9") (pinfunction "PIO1_30/FC7_TXD_SCL_MISO_WS/SD0_D7/SCT_GPI7/USB1_OVERCURRENTN/USB1_LEDN/PLU_IN1_F9") (pintype "passive+no_connect"))
    )
    (net (code "93") (name "unconnected-(U5-PIO1_31{slash}MCLK{slash}SD1_CLK{slash}CTIMER0_MAT2{slash}SCT0_OUT6{slash}PLU_IN0-PadH6)") (class "Default")
      (node (ref "U5") (pin "H6") (pinfunction "PIO1_31/MCLK/SD1_CLK/CTIMER0_MAT2/SCT0_OUT6/PLU_IN0_H6") (pintype "passive+no_connect"))
    )
    (net (code "94") (name "unconnected-(U5-USB1_3V3-PadN7)") (class "Default")
      (node (ref "U5") (pin "N7") (pinfunction "USB1_3V3_N7") (pintype "passive+no_connect"))
    )
    (net (code "95") (name "unconnected-(U5-USB1_DM-PadN6)") (class "Default")
      (node (ref "U5") (pin "N6") (pinfunction "USB1_DM_N6") (pintype "passive+no_connect"))
    )
    (net (code "96") (name "unconnected-(U5-USB1_DP-PadM6)") (class "Default")
      (node (ref "U5") (pin "M6") (pinfunction "USB1_DP_M6") (pintype "passive+no_connect"))
    )
    (net (code "97") (name "unconnected-(U5-USB1_VBUS-PadN8)") (class "Default")
      (node (ref "U5") (pin "N8") (pinfunction "USB1_VBUS_N8") (pintype "passive+no_connect"))
    )
    (net (code "98") (name "unconnected-(U5-XTAL32K_N-PadJ12)") (class "Default")
      (node (ref "U5") (pin "J12") (pinfunction "XTAL32K_N_J12") (pintype "passive+no_connect"))
    )
    (net (code "99") (name "unconnected-(U5-XTAL32K_P-PadJ13)") (class "Default")
      (node (ref "U5") (pin "J13") (pinfunction "XTAL32K_P_J13") (pintype "passive+no_connect"))
    )
  )
)
